# ME6408_Flip_Clock.net
KiCad netlist of a schematic drawn in EAGLE
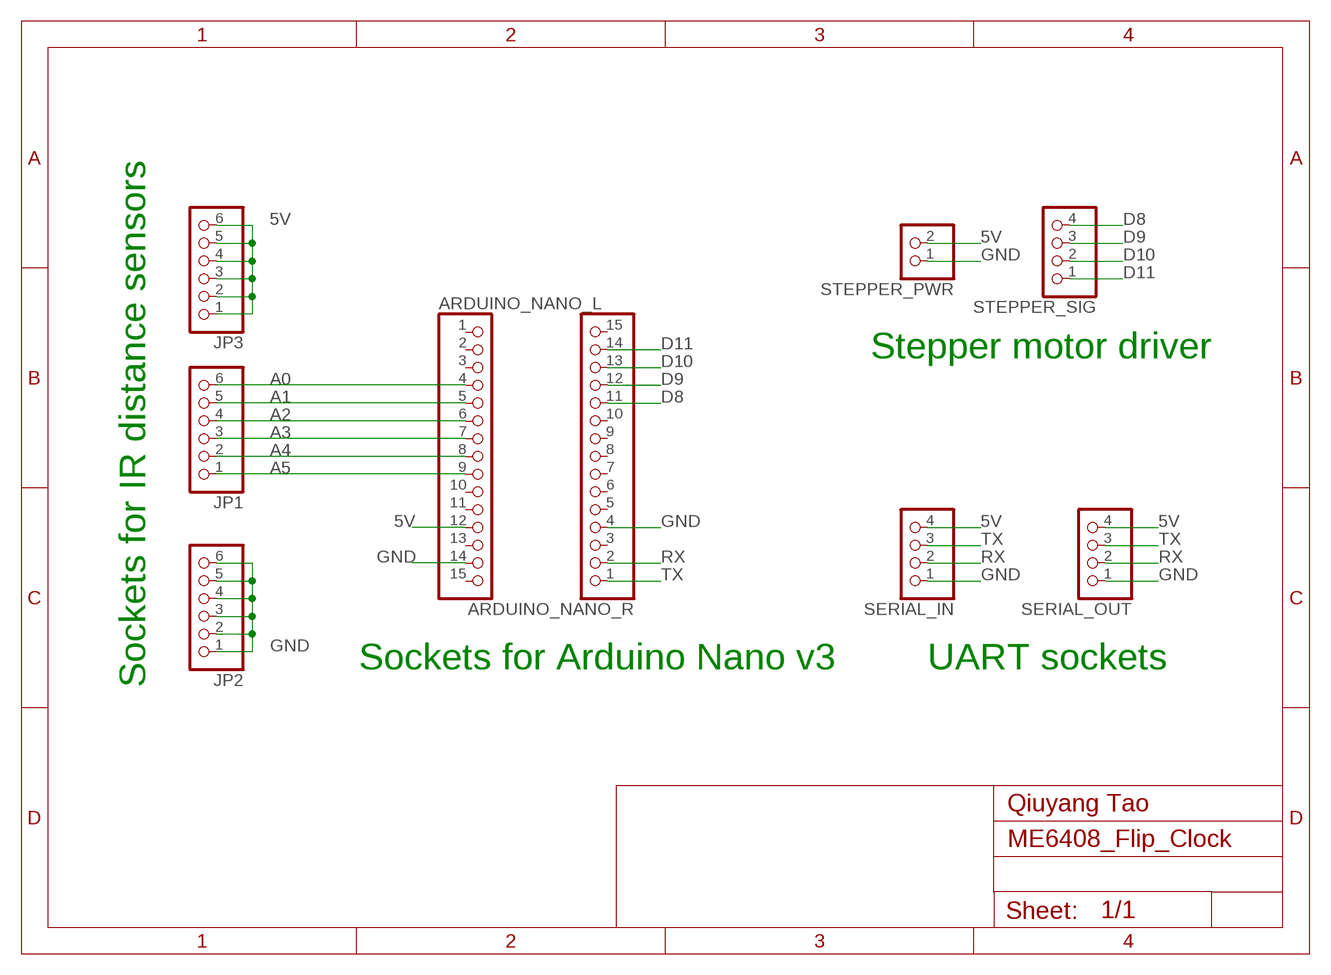
[diagram p0: schematic, sheet 1]

(export (version "E")
  (design (tool "Eeschema 10.0.6"))
  (components
    (comp (ref "ARDUINO_NANO_L")
      (value "PINHD-1X15")
      (footprint "eagle-import:1X15")
      (libsource (lib "eagle-import") (part "PINHD-1X15"))
    )
    (comp (ref "ARDUINO_NANO_R")
      (value "PINHD-1X15")
      (footprint "eagle-import:1X15")
      (libsource (lib "eagle-import") (part "PINHD-1X15"))
    )
    (comp (ref "JP1")
      (value "PINHD-1X6")
      (footprint "eagle-import:1X06")
      (libsource (lib "eagle-import") (part "PINHD-1X6"))
    )
    (comp (ref "JP2")
      (value "PINHD-1X6")
      (footprint "eagle-import:1X06")
      (libsource (lib "eagle-import") (part "PINHD-1X6"))
    )
    (comp (ref "JP3")
      (value "PINHD-1X6")
      (footprint "eagle-import:1X06")
      (libsource (lib "eagle-import") (part "PINHD-1X6"))
    )
    (comp (ref "SERIAL_IN")
      (value "PINHD-1X4")
      (footprint "eagle-import:1X04")
      (libsource (lib "eagle-import") (part "PINHD-1X4"))
    )
    (comp (ref "SERIAL_OUT")
      (value "PINHD-1X4")
      (footprint "eagle-import:1X04")
      (libsource (lib "eagle-import") (part "PINHD-1X4"))
    )
    (comp (ref "STEPPER_PWR")
      (value "PINHD-1X2")
      (footprint "eagle-import:1X02")
      (libsource (lib "eagle-import") (part "PINHD-1X2"))
    )
    (comp (ref "STEPPER_SIG")
      (value "PINHD-1X4")
      (footprint "eagle-import:1X04")
      (libsource (lib "eagle-import") (part "PINHD-1X4"))
    )
  )
  (nets
    (net (code "1") (name "/5V") (class "Default")
      (node (ref "ARDUINO_NANO_L") (pin "12") (pinfunction "12_12") (pintype "passive"))
      (node (ref "JP3") (pin "1") (pinfunction "1_1") (pintype "passive"))
      (node (ref "JP3") (pin "2") (pinfunction "2_2") (pintype "passive"))
      (node (ref "JP3") (pin "3") (pinfunction "3_3") (pintype "passive"))
      (node (ref "JP3") (pin "4") (pinfunction "4_4") (pintype "passive"))
      (node (ref "JP3") (pin "5") (pinfunction "5_5") (pintype "passive"))
      (node (ref "JP3") (pin "6") (pinfunction "6_6") (pintype "passive"))
      (node (ref "SERIAL_IN") (pin "4") (pinfunction "4_4") (pintype "passive"))
      (node (ref "SERIAL_OUT") (pin "4") (pinfunction "4_4") (pintype "passive"))
      (node (ref "STEPPER_PWR") (pin "2") (pinfunction "2_2") (pintype "passive"))
    )
    (net (code "2") (name "/A0") (class "Default")
      (node (ref "ARDUINO_NANO_L") (pin "4") (pinfunction "4_4") (pintype "passive"))
      (node (ref "JP1") (pin "6") (pinfunction "6_6") (pintype "passive"))
    )
    (net (code "3") (name "/A1") (class "Default")
      (node (ref "ARDUINO_NANO_L") (pin "5") (pinfunction "5_5") (pintype "passive"))
      (node (ref "JP1") (pin "5") (pinfunction "5_5") (pintype "passive"))
    )
    (net (code "4") (name "/A2") (class "Default")
      (node (ref "ARDUINO_NANO_L") (pin "6") (pinfunction "6_6") (pintype "passive"))
      (node (ref "JP1") (pin "4") (pinfunction "4_4") (pintype "passive"))
    )
    (net (code "5") (name "/A3") (class "Default")
      (node (ref "ARDUINO_NANO_L") (pin "7") (pinfunction "7_7") (pintype "passive"))
      (node (ref "JP1") (pin "3") (pinfunction "3_3") (pintype "passive"))
    )
    (net (code "6") (name "/A4") (class "Default")
      (node (ref "ARDUINO_NANO_L") (pin "8") (pinfunction "8_8") (pintype "passive"))
      (node (ref "JP1") (pin "2") (pinfunction "2_2") (pintype "passive"))
    )
    (net (code "7") (name "/A5") (class "Default")
      (node (ref "ARDUINO_NANO_L") (pin "9") (pinfunction "9_9") (pintype "passive"))
      (node (ref "JP1") (pin "1") (pinfunction "1_1") (pintype "passive"))
    )
    (net (code "8") (name "/D8") (class "Default")
      (node (ref "ARDUINO_NANO_R") (pin "11") (pinfunction "11_11") (pintype "passive"))
      (node (ref "STEPPER_SIG") (pin "4") (pinfunction "4_4") (pintype "passive"))
    )
    (net (code "9") (name "/D9") (class "Default")
      (node (ref "ARDUINO_NANO_R") (pin "12") (pinfunction "12_12") (pintype "passive"))
      (node (ref "STEPPER_SIG") (pin "3") (pinfunction "3_3") (pintype "passive"))
    )
    (net (code "10") (name "/D10") (class "Default")
      (node (ref "ARDUINO_NANO_R") (pin "13") (pinfunction "13_13") (pintype "passive"))
      (node (ref "STEPPER_SIG") (pin "2") (pinfunction "2_2") (pintype "passive"))
    )
    (net (code "11") (name "/D11") (class "Default")
      (node (ref "ARDUINO_NANO_R") (pin "14") (pinfunction "14_14") (pintype "passive"))
      (node (ref "STEPPER_SIG") (pin "1") (pinfunction "1_1") (pintype "passive"))
    )
    (net (code "12") (name "/GND") (class "Default")
      (node (ref "ARDUINO_NANO_L") (pin "14") (pinfunction "14_14") (pintype "passive"))
      (node (ref "ARDUINO_NANO_R") (pin "4") (pinfunction "4_4") (pintype "passive"))
      (node (ref "JP2") (pin "1") (pinfunction "1_1") (pintype "passive"))
      (node (ref "JP2") (pin "2") (pinfunction "2_2") (pintype "passive"))
      (node (ref "JP2") (pin "3") (pinfunction "3_3") (pintype "passive"))
      (node (ref "JP2") (pin "4") (pinfunction "4_4") (pintype "passive"))
      (node (ref "JP2") (pin "5") (pinfunction "5_5") (pintype "passive"))
      (node (ref "JP2") (pin "6") (pinfunction "6_6") (pintype "passive"))
      (node (ref "SERIAL_IN") (pin "1") (pinfunction "1_1") (pintype "passive"))
      (node (ref "SERIAL_OUT") (pin "1") (pinfunction "1_1") (pintype "passive"))
      (node (ref "STEPPER_PWR") (pin "1") (pinfunction "1_1") (pintype "passive"))
    )
    (net (code "13") (name "/RX") (class "Default")
      (node (ref "ARDUINO_NANO_R") (pin "2") (pinfunction "2_2") (pintype "passive"))
      (node (ref "SERIAL_IN") (pin "2") (pinfunction "2_2") (pintype "passive"))
      (node (ref "SERIAL_OUT") (pin "2") (pinfunction "2_2") (pintype "passive"))
    )
    (net (code "14") (name "/TX") (class "Default")
      (node (ref "ARDUINO_NANO_R") (pin "1") (pinfunction "1_1") (pintype "passive"))
      (node (ref "SERIAL_IN") (pin "3") (pinfunction "3_3") (pintype "passive"))
      (node (ref "SERIAL_OUT") (pin "3") (pinfunction "3_3") (pintype "passive"))
    )
    (net (code "15") (name "unconnected-(ARDUINO_NANO_L-Pad1)") (class "Default")
      (node (ref "ARDUINO_NANO_L") (pin "1") (pinfunction "1_1") (pintype "passive"))
    )
    (net (code "16") (name "unconnected-(ARDUINO_NANO_L-Pad2)") (class "Default")
      (node (ref "ARDUINO_NANO_L") (pin "2") (pinfunction "2_2") (pintype "passive"))
    )
    (net (code "17") (name "unconnected-(ARDUINO_NANO_L-Pad3)") (class "Default")
      (node (ref "ARDUINO_NANO_L") (pin "3") (pinfunction "3_3") (pintype "passive"))
    )
    (net (code "18") (name "unconnected-(ARDUINO_NANO_L-Pad10)") (class "Default")
      (node (ref "ARDUINO_NANO_L") (pin "10") (pinfunction "10_10") (pintype "passive"))
    )
    (net (code "19") (name "unconnected-(ARDUINO_NANO_L-Pad11)") (class "Default")
      (node (ref "ARDUINO_NANO_L") (pin "11") (pinfunction "11_11") (pintype "passive"))
    )
    (net (code "20") (name "unconnected-(ARDUINO_NANO_L-Pad13)") (class "Default")
      (node (ref "ARDUINO_NANO_L") (pin "13") (pinfunction "13_13") (pintype "passive"))
    )
    (net (code "21") (name "unconnected-(ARDUINO_NANO_L-Pad15)") (class "Default")
      (node (ref "ARDUINO_NANO_L") (pin "15") (pinfunction "15_15") (pintype "passive"))
    )
    (net (code "22") (name "unconnected-(ARDUINO_NANO_R-Pad3)") (class "Default")
      (node (ref "ARDUINO_NANO_R") (pin "3") (pinfunction "3_3") (pintype "passive"))
    )
    (net (code "23") (name "unconnected-(ARDUINO_NANO_R-Pad5)") (class "Default")
      (node (ref "ARDUINO_NANO_R") (pin "5") (pinfunction "5_5") (pintype "passive"))
    )
    (net (code "24") (name "unconnected-(ARDUINO_NANO_R-Pad6)") (class "Default")
      (node (ref "ARDUINO_NANO_R") (pin "6") (pinfunction "6_6") (pintype "passive"))
    )
    (net (code "25") (name "unconnected-(ARDUINO_NANO_R-Pad7)") (class "Default")
      (node (ref "ARDUINO_NANO_R") (pin "7") (pinfunction "7_7") (pintype "passive"))
    )
    (net (code "26") (name "unconnected-(ARDUINO_NANO_R-Pad8)") (class "Default")
      (node (ref "ARDUINO_NANO_R") (pin "8") (pinfunction "8_8") (pintype "passive"))
    )
    (net (code "27") (name "unconnected-(ARDUINO_NANO_R-Pad9)") (class "Default")
      (node (ref "ARDUINO_NANO_R") (pin "9") (pinfunction "9_9") (pintype "passive"))
    )
    (net (code "28") (name "unconnected-(ARDUINO_NANO_R-Pad10)") (class "Default")
      (node (ref "ARDUINO_NANO_R") (pin "10") (pinfunction "10_10") (pintype "passive"))
    )
    (net (code "29") (name "unconnected-(ARDUINO_NANO_R-Pad15)") (class "Default")
      (node (ref "ARDUINO_NANO_R") (pin "15") (pinfunction "15_15") (pintype "passive"))
    )
  )
)
